# SensorBoard.net
KiCad netlist of a schematic drawn in Altium Designer
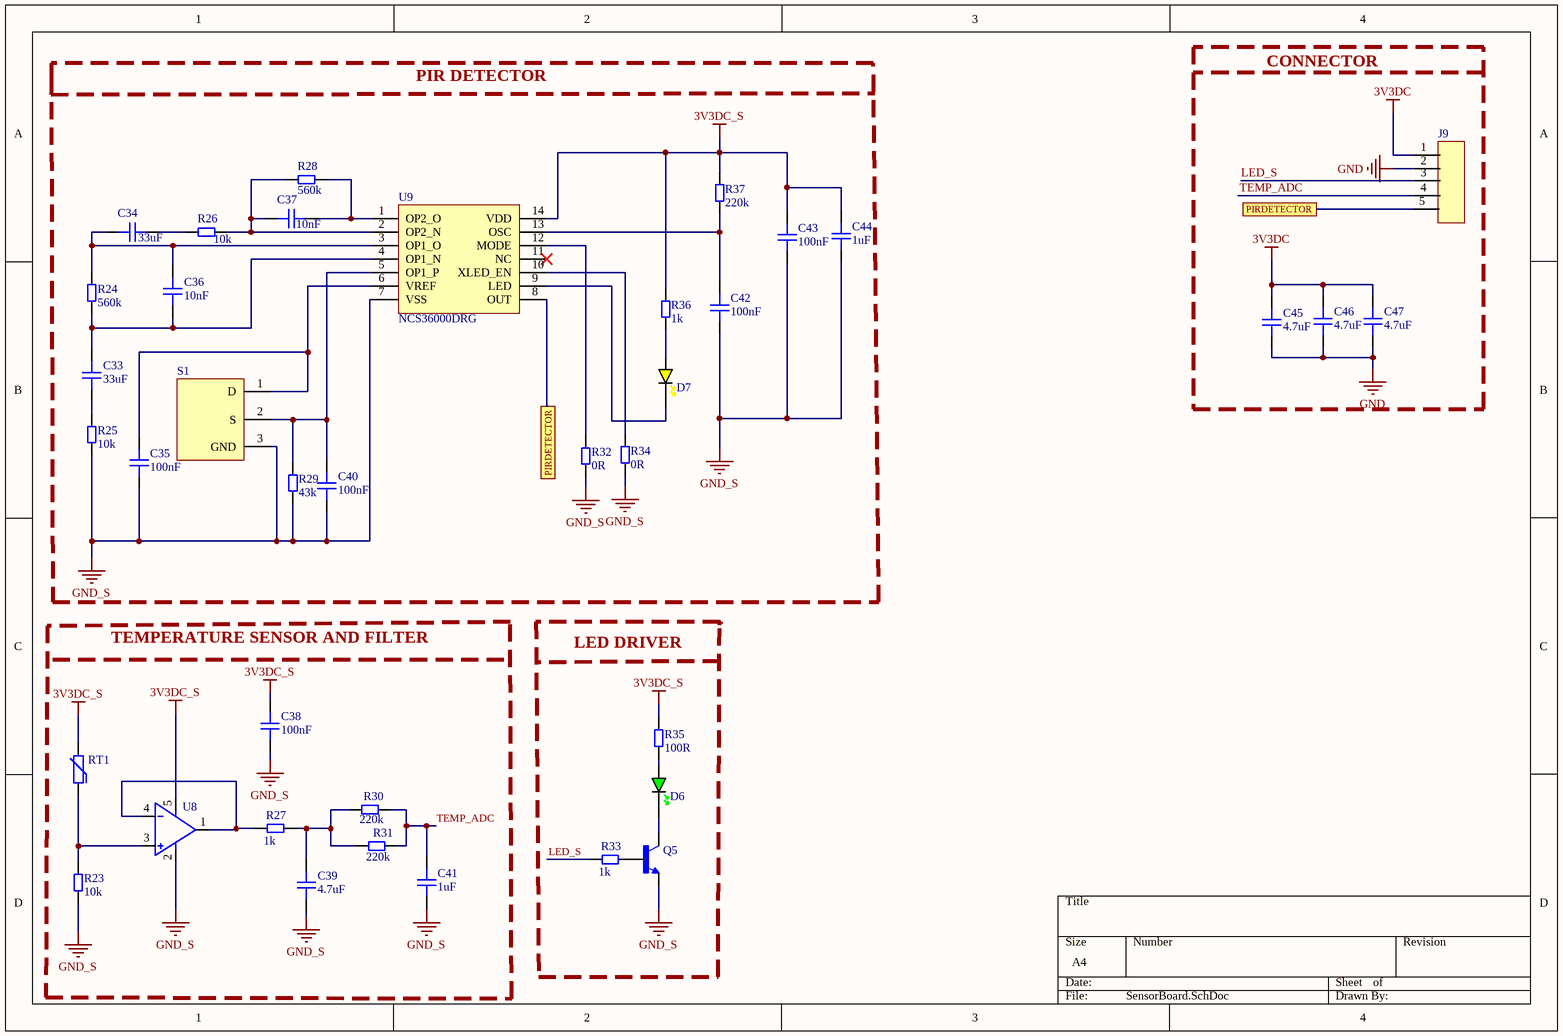
[diagram p0: SensorBoard.SchDoc]

(export (version "E")
  (design (tool "Eeschema 10.0.6"))
  (components
    (comp (ref "C33")
      (value "33uF")
      (footprint "CAP_0603")
      (description "Capacitor SMD 0603 10V")
      (libsource (lib "Integrated_Library1") (part "CAP_0603_10V"))
    )
    (comp (ref "C34")
      (value "33uF")
      (footprint "CAP_0603")
      (description "Capacitor SMD 0603 10V")
      (libsource (lib "Integrated_Library1") (part "CAP_0603_10V"))
    )
    (comp (ref "C35")
      (value "100nF")
      (footprint "CAP_0603")
      (description "Capacitor SMD 0603 10V")
      (libsource (lib "Integrated_Library1") (part "CAP_0603_10V"))
    )
    (comp (ref "C36")
      (value "10nF")
      (footprint "CAP_0603")
      (description "Capacitor SMD 0603 10V")
      (libsource (lib "Integrated_Library1") (part "CAP_0603_10V"))
    )
    (comp (ref "C37")
      (value "10nF")
      (footprint "CAP_0603")
      (description "Capacitor SMD 0603 10V")
      (libsource (lib "Integrated_Library1") (part "CAP_0603_10V"))
    )
    (comp (ref "C38")
      (value "100nF")
      (footprint "CAP_0603")
      (description "Capacitor SMD 0603 10V")
      (libsource (lib "Integrated_Library1") (part "CAP_0603_10V"))
    )
    (comp (ref "C39")
      (value "4.7uF")
      (footprint "CAP_0603")
      (description "Capacitor SMD 0603 10V")
      (libsource (lib "Integrated_Library1") (part "CAP_0603_10V"))
    )
    (comp (ref "C40")
      (value "100nF")
      (footprint "CAP_0603")
      (description "Capacitor SMD 0603 10V")
      (libsource (lib "Integrated_Library1") (part "CAP_0603_10V"))
    )
    (comp (ref "C41")
      (value "1uF")
      (footprint "CAP_0603")
      (description "Capacitor SMD 0603 10V")
      (libsource (lib "Integrated_Library1") (part "CAP_0603_10V"))
    )
    (comp (ref "C42")
      (value "100nF")
      (footprint "CAP_0603")
      (description "Capacitor SMD 0603 10V")
      (libsource (lib "Integrated_Library1") (part "CAP_0603_10V"))
    )
    (comp (ref "C43")
      (value "100nF")
      (footprint "CAP_0603")
      (description "Capacitor SMD 0603 10V")
      (libsource (lib "Integrated_Library1") (part "CAP_0603_10V"))
    )
    (comp (ref "C44")
      (value "1uF")
      (footprint "CAP_0603")
      (description "Capacitor SMD 0603 10V")
      (libsource (lib "Integrated_Library1") (part "CAP_0603_10V"))
    )
    (comp (ref "C45")
      (value "4.7uF")
      (footprint "CAP_0603")
      (description "Capacitor SMD 0603 10V")
      (libsource (lib "Integrated_Library1") (part "CAP_0603_10V"))
    )
    (comp (ref "C46")
      (value "4.7uF")
      (footprint "CAP_0603")
      (description "Capacitor SMD 0603 10V")
      (libsource (lib "Integrated_Library1") (part "CAP_0603_10V"))
    )
    (comp (ref "C47")
      (value "4.7uF")
      (footprint "CAP_0603")
      (description "Capacitor SMD 0603 10V")
      (libsource (lib "Integrated_Library1") (part "CAP_0603_10V"))
    )
    (comp (ref "D6")
      (value "GREEN")
      (footprint "LED_0603_GREEN")
      (description "LED 0603 GREEN SMD")
      (fields (field (name "DESIGNER") "ZehraOzkan"))
      (libsource (lib "Integrated_Library1") (part "LED_0603_GREEN"))
    )
    (comp (ref "D7")
      (value "YELLOW")
      (footprint "LED_0603_YELLOW")
      (description "LED 0603 YELLOW SMD")
      (fields (field (name "DESIGNER") "ZehraOzkan"))
      (libsource (lib "Integrated_Library1") (part "LED_0603_YELLOW"))
    )
    (comp (ref "J9")
      (value "Terminal_Block_Header")
      (footprint "HEADER_5")
      (description "5 pin Female")
      (fields (field (name "DESIGNER") "ZehraOzkan"))
      (libsource (lib "Integrated_Library1") (part "Terminal_Block_Header"))
    )
    (comp (ref "Q5")
      (value "BC237")
      (footprint "BC237")
      (description "Transistor NPN BC237B MOTOROLA milliampere=100 V=45 R204")
      (fields
        (field (name "MANUFACTURER") "ON Semiconductor / Fairchild")
        (field (name "MANUFACTURER PART NUMBER") "BC237B")
        (field (name "DESIGNER") "ZehraOzkan")
      )
      (libsource (lib "Integrated_Library1") (part "BC237"))
    )
    (comp (ref "R23")
      (value "10k")
      (footprint "RES-0805")
      (description "Res SMD 0805 10K 1% 0.125W T.C.100PPM")
      (fields
        (field (name "MANUFACTURER") "Yageo")
        (field (name "MANUFACTURER PART NUMBER") "RC0805FR-0710KL")
        (field (name "DESIGNER") "ZehraOzkan")
      )
      (libsource (lib "Integrated_Library1") (part "RES-0805-10k"))
    )
    (comp (ref "R24")
      (value "560k")
      (footprint "RES-0805")
      (description "Res SMD 0805 10K 1% 0.125W T.C.100PPM")
      (fields
        (field (name "MANUFACTURER") "Yageo")
        (field (name "MANUFACTURER PART NUMBER") "RC0805FR-0710KL")
        (field (name "DESIGNER") "ZehraOzkan")
      )
      (libsource (lib "Integrated_Library1") (part "RES-0805-10k"))
    )
    (comp (ref "R25")
      (value "10k")
      (footprint "RES-0805")
      (description "Res SMD 0805 10K 1% 0.125W T.C.100PPM")
      (fields
        (field (name "MANUFACTURER") "Yageo")
        (field (name "MANUFACTURER PART NUMBER") "RC0805FR-0710KL")
        (field (name "DESIGNER") "ZehraOzkan")
      )
      (libsource (lib "Integrated_Library1") (part "RES-0805-10k"))
    )
    (comp (ref "R26")
      (value "10k")
      (footprint "RES-0805")
      (description "Res SMD 0805 10K 1% 0.125W T.C.100PPM")
      (fields
        (field (name "MANUFACTURER") "Yageo")
        (field (name "MANUFACTURER PART NUMBER") "RC0805FR-0710KL")
        (field (name "DESIGNER") "ZehraOzkan")
      )
      (libsource (lib "Integrated_Library1") (part "RES-0805-10k"))
    )
    (comp (ref "R27")
      (value "1k")
      (footprint "RES-0805")
      (description "Res SMD 0805 10K 1% 0.125W T.C.100PPM")
      (fields
        (field (name "MANUFACTURER") "Yageo")
        (field (name "MANUFACTURER PART NUMBER") "RC0805FR-0710KL")
        (field (name "DESIGNER") "ZehraOzkan")
      )
      (libsource (lib "Integrated_Library1") (part "RES-0805-10k"))
    )
    (comp (ref "R28")
      (value "560k")
      (footprint "RES-0805")
      (description "Res SMD 0805 10K 1% 0.125W T.C.100PPM")
      (fields
        (field (name "MANUFACTURER") "Yageo")
        (field (name "MANUFACTURER PART NUMBER") "RC0805FR-0710KL")
        (field (name "DESIGNER") "ZehraOzkan")
      )
      (libsource (lib "Integrated_Library1") (part "RES-0805-10k"))
    )
    (comp (ref "R29")
      (value "43k")
      (footprint "RES-0805")
      (description "Res SMD 0805 10K 1% 0.125W T.C.100PPM")
      (fields
        (field (name "MANUFACTURER") "Yageo")
        (field (name "MANUFACTURER PART NUMBER") "RC0805FR-0710KL")
        (field (name "DESIGNER") "ZehraOzkan")
      )
      (libsource (lib "Integrated_Library1") (part "RES-0805-10k"))
    )
    (comp (ref "R30")
      (value "220k")
      (footprint "RES-0805")
      (description "Res SMD 0805 10K 1% 0.125W T.C.100PPM")
      (fields
        (field (name "MANUFACTURER") "Yageo")
        (field (name "MANUFACTURER PART NUMBER") "RC0805FR-0710KL")
        (field (name "DESIGNER") "ZehraOzkan")
      )
      (libsource (lib "Integrated_Library1") (part "RES-0805-10k"))
    )
    (comp (ref "R31")
      (value "220k")
      (footprint "RES-0805")
      (description "Res SMD 0805 10K 1% 0.125W T.C.100PPM")
      (fields
        (field (name "MANUFACTURER") "Yageo")
        (field (name "MANUFACTURER PART NUMBER") "RC0805FR-0710KL")
        (field (name "DESIGNER") "ZehraOzkan")
      )
      (libsource (lib "Integrated_Library1") (part "RES-0805-10k"))
    )
    (comp (ref "R32")
      (value "0R")
      (footprint "RES-0805")
      (description "Res SMD 0805 10K 1% 0.125W T.C.100PPM")
      (fields
        (field (name "MANUFACTURER") "Yageo")
        (field (name "MANUFACTURER PART NUMBER") "RC0805FR-0710KL")
        (field (name "DESIGNER") "ZehraOzkan")
      )
      (libsource (lib "Integrated_Library1") (part "RES-0805-10k"))
    )
    (comp (ref "R33")
      (value "1k")
      (footprint "RES-0805")
      (description "Res SMD 0805 10K 1% 0.125W T.C.100PPM")
      (fields
        (field (name "MANUFACTURER") "Yageo")
        (field (name "MANUFACTURER PART NUMBER") "RC0805FR-0710KL")
        (field (name "DESIGNER") "ZehraOzkan")
      )
      (libsource (lib "Integrated_Library1") (part "RES-0805-10k"))
    )
    (comp (ref "R34")
      (value "0R")
      (footprint "RES-0805")
      (description "Res SMD 0805 10K 1% 0.125W T.C.100PPM")
      (fields
        (field (name "MANUFACTURER") "Yageo")
        (field (name "MANUFACTURER PART NUMBER") "RC0805FR-0710KL")
        (field (name "DESIGNER") "ZehraOzkan")
      )
      (libsource (lib "Integrated_Library1") (part "RES-0805-10k"))
    )
    (comp (ref "R35")
      (value "100R")
      (footprint "RES-0805")
      (description "Res SMD 0805 10K 1% 0.125W T.C.100PPM")
      (fields
        (field (name "MANUFACTURER") "Yageo")
        (field (name "MANUFACTURER PART NUMBER") "RC0805FR-0710KL")
        (field (name "DESIGNER") "ZehraOzkan")
      )
      (libsource (lib "Integrated_Library1") (part "RES-0805-10k"))
    )
    (comp (ref "R36")
      (value "1k")
      (footprint "RES-0805")
      (description "Res SMD 0805 10K 1% 0.125W T.C.100PPM")
      (fields
        (field (name "MANUFACTURER") "Yageo")
        (field (name "MANUFACTURER PART NUMBER") "RC0805FR-0710KL")
        (field (name "DESIGNER") "ZehraOzkan")
      )
      (libsource (lib "Integrated_Library1") (part "RES-0805-10k"))
    )
    (comp (ref "R37")
      (value "220k")
      (footprint "RES-0805")
      (description "Res SMD 0805 10K 1% 0.125W T.C.100PPM")
      (fields
        (field (name "MANUFACTURER") "Yageo")
        (field (name "MANUFACTURER PART NUMBER") "RC0805FR-0710KL")
        (field (name "DESIGNER") "ZehraOzkan")
      )
      (libsource (lib "Integrated_Library1") (part "RES-0805-10k"))
    )
    (comp (ref "RT1")
      (value "TFPT1206L1002FM")
      (footprint "RES_1206")
      (description "Thermistor PTC 10K Ohm 1% 2-Pin 1206 Surface Mount Solder Pad T/R Automotive")
      (fields
        (field (name "MANUFACTURER") "Vishay Dale")
        (field (name "TOLERANCE") "1%")
        (field (name "DESIGNER") "ZehraOzkan")
      )
      (libsource (lib "Integrated_Library1") (part "TFPT1206L1002FM"))
    )
    (comp (ref "S1")
      (value "LHI 878/3902")
      (footprint "LHI 878")
      (description "SENSOR PYRO DETECTOR DUAL MOTION")
      (fields
        (field (name "MANUFACTURER") "Excelitas")
        (field (name "MANUFACTURER PART NUMBER") "LHI878/3902")
        (field (name "DESIGNER") "ZehraOzkan")
      )
      (libsource (lib "Integrated_Library1") (part "LHI 878/3902"))
    )
    (comp (ref "U8")
      (value "OPA314AIDBVR")
      (footprint "SOT-23-5")
      (description "IC OPAMP GP 3MHZ RRO SOT23-5")
      (fields (field (name "MANUFACTURER") "Texas Instruments") (field (name "DESIGNER") "ZehraOzkan"))
      (libsource (lib "Integrated_Library1") (part "OPA314AIDBVR"))
    )
    (comp (ref "U9")
      (value "NCS36000DRG")
      (footprint "SOIC-14")
      (description "NCS36000 Series Single 5.75V Passive Infrared Detector Controller (PIR) -SOIC-14")
      (fields (field (name "MANUFACTURER") "ON Semiconductor") (field (name "DESIGNER") "ZehraOzkan"))
      (libsource (lib "Integrated_Library1") (part "NCS36000DRG"))
    )
  )
  (nets
    (net (code "1") (name "/LED_S") (class "Default")
      (node (ref "J9") (pin "3") (pinfunction "3_3") (pintype "passive"))
      (node (ref "R33") (pin "2") (pinfunction "2_2") (pintype "passive"))
    )
    (net (code "2") (name "/PIRDETECTOR") (class "Default")
      (node (ref "J9") (pin "5") (pinfunction "5_5") (pintype "passive"))
      (node (ref "U9") (pin "8") (pinfunction "OUT_8") (pintype "passive"))
    )
    (net (code "3") (name "/TEMP_ADC") (class "Default")
      (node (ref "C41") (pin "2") (pinfunction "2_2") (pintype "passive"))
      (node (ref "J9") (pin "4") (pinfunction "4_4") (pintype "passive"))
      (node (ref "R30") (pin "1") (pinfunction "1_1") (pintype "passive"))
      (node (ref "R31") (pin "1") (pinfunction "1_1") (pintype "passive"))
    )
    (net (code "4") (name "3V3DC") (class "Default")
      (node (ref "C45") (pin "2") (pinfunction "2_2") (pintype "passive"))
      (node (ref "C46") (pin "2") (pinfunction "2_2") (pintype "passive"))
      (node (ref "C47") (pin "2") (pinfunction "2_2") (pintype "passive"))
      (node (ref "J9") (pin "1") (pinfunction "1_1") (pintype "passive"))
    )
    (net (code "5") (name "3V3DC_S") (class "Default")
      (node (ref "C38") (pin "2") (pinfunction "2_2") (pintype "passive"))
      (node (ref "C43") (pin "2") (pinfunction "2_2") (pintype "passive"))
      (node (ref "C44") (pin "2") (pinfunction "2_2") (pintype "passive"))
      (node (ref "R35") (pin "1") (pinfunction "1_1") (pintype "passive"))
      (node (ref "R36") (pin "1") (pinfunction "1_1") (pintype "passive"))
      (node (ref "R37") (pin "1") (pinfunction "1_1") (pintype "passive"))
      (node (ref "RT1") (pin "2") (pinfunction "2_2") (pintype "passive"))
      (node (ref "U8") (pin "5") (pintype "passive"))
      (node (ref "U9") (pin "14") (pinfunction "VDD_14") (pintype "passive"))
    )
    (net (code "6") (name "GND") (class "Default")
      (node (ref "C45") (pin "1") (pinfunction "1_1") (pintype "passive"))
      (node (ref "C46") (pin "1") (pinfunction "1_1") (pintype "passive"))
      (node (ref "C47") (pin "1") (pinfunction "1_1") (pintype "passive"))
      (node (ref "J9") (pin "2") (pinfunction "2_2") (pintype "passive"))
    )
    (net (code "7") (name "GND_S") (class "Default")
      (node (ref "C35") (pin "2") (pinfunction "2_2") (pintype "passive"))
      (node (ref "C38") (pin "1") (pinfunction "1_1") (pintype "passive"))
      (node (ref "C39") (pin "1") (pinfunction "1_1") (pintype "passive"))
      (node (ref "C40") (pin "2") (pinfunction "2_2") (pintype "passive"))
      (node (ref "C41") (pin "1") (pinfunction "1_1") (pintype "passive"))
      (node (ref "C42") (pin "1") (pinfunction "1_1") (pintype "passive"))
      (node (ref "C43") (pin "1") (pinfunction "1_1") (pintype "passive"))
      (node (ref "C44") (pin "1") (pinfunction "1_1") (pintype "passive"))
      (node (ref "Q5") (pin "1") (pinfunction "E_1") (pintype "passive"))
      (node (ref "R23") (pin "1") (pinfunction "1_1") (pintype "passive"))
      (node (ref "R25") (pin "1") (pinfunction "1_1") (pintype "passive"))
      (node (ref "R29") (pin "1") (pinfunction "1_1") (pintype "passive"))
      (node (ref "R32") (pin "2") (pinfunction "2_2") (pintype "passive"))
      (node (ref "R34") (pin "2") (pinfunction "2_2") (pintype "passive"))
      (node (ref "S1") (pin "3") (pinfunction "GND_3") (pintype "passive"))
      (node (ref "U8") (pin "2") (pintype "passive"))
      (node (ref "U9") (pin "7") (pinfunction "VSS_7") (pintype "passive"))
    )
    (net (code "8") (name "Net-(C33-Pad2)") (class "Default")
      (node (ref "C33") (pin "2") (pinfunction "2_2") (pintype "passive"))
      (node (ref "R25") (pin "2") (pinfunction "2_2") (pintype "passive"))
    )
    (net (code "9") (name "Net-(C34-Pad1)") (class "Default")
      (node (ref "C34") (pin "1") (pinfunction "1_1") (pintype "passive"))
      (node (ref "R26") (pin "1") (pinfunction "1_1") (pintype "passive"))
    )
    (net (code "10") (name "Net-(C39-Pad2)") (class "Default")
      (node (ref "C39") (pin "2") (pinfunction "2_2") (pintype "passive"))
      (node (ref "R27") (pin "1") (pinfunction "1_1") (pintype "passive"))
      (node (ref "R30") (pin "2") (pinfunction "2_2") (pintype "passive"))
      (node (ref "R31") (pin "2") (pinfunction "2_2") (pintype "passive"))
    )
    (net (code "11") (name "Net-(D6-PadA)") (class "Default")
      (node (ref "D6") (pin "A") (pinfunction "A_A") (pintype "passive"))
      (node (ref "R35") (pin "2") (pinfunction "2_2") (pintype "passive"))
    )
    (net (code "12") (name "Net-(D7-PadA)") (class "Default")
      (node (ref "D7") (pin "A") (pinfunction "A_A") (pintype "passive"))
      (node (ref "R36") (pin "2") (pinfunction "2_2") (pintype "passive"))
    )
    (net (code "13") (name "Net-(Q5-B)") (class "Default")
      (node (ref "Q5") (pin "2") (pinfunction "B_2") (pintype "passive"))
      (node (ref "R33") (pin "1") (pinfunction "1_1") (pintype "passive"))
    )
    (net (code "14") (name "Net-(Q5-C)") (class "Default")
      (node (ref "D6") (pin "K") (pinfunction "K_K") (pintype "passive"))
      (node (ref "Q5") (pin "3") (pinfunction "C_3") (pintype "passive"))
    )
    (net (code "15") (name "Net-(R23-Pad2)") (class "Default")
      (node (ref "R23") (pin "2") (pinfunction "2_2") (pintype "passive"))
      (node (ref "RT1") (pin "1") (pinfunction "1_1") (pintype "passive"))
      (node (ref "U8") (pin "3") (pintype "passive"))
    )
    (net (code "16") (name "Net-(R27-Pad2)") (class "Default")
      (node (ref "R27") (pin "2") (pinfunction "2_2") (pintype "passive"))
      (node (ref "U8") (pin "1") (pintype "passive"))
      (node (ref "U8") (pin "4") (pintype "passive"))
    )
    (net (code "17") (name "Net-(S1-D)") (class "Default")
      (node (ref "C35") (pin "1") (pinfunction "1_1") (pintype "passive"))
      (node (ref "S1") (pin "1") (pinfunction "D_1") (pintype "passive"))
      (node (ref "U9") (pin "6") (pinfunction "VREF_6") (pintype "passive"))
    )
    (net (code "18") (name "Net-(S1-S)") (class "Default")
      (node (ref "C40") (pin "1") (pinfunction "1_1") (pintype "passive"))
      (node (ref "R29") (pin "2") (pinfunction "2_2") (pintype "passive"))
      (node (ref "S1") (pin "2") (pinfunction "S_2") (pintype "passive"))
      (node (ref "U9") (pin "5") (pinfunction "OP1_P_5") (pintype "passive"))
    )
    (net (code "19") (name "Net-(U9-LED)") (class "Default")
      (node (ref "D7") (pin "K") (pinfunction "K_K") (pintype "passive"))
      (node (ref "U9") (pin "9") (pinfunction "LED_9") (pintype "passive"))
    )
    (net (code "20") (name "Net-(U9-MODE)") (class "Default")
      (node (ref "R32") (pin "1") (pinfunction "1_1") (pintype "passive"))
      (node (ref "U9") (pin "12") (pinfunction "MODE_12") (pintype "passive"))
    )
    (net (code "21") (name "Net-(U9-OP1_N)") (class "Default")
      (node (ref "C33") (pin "1") (pinfunction "1_1") (pintype "passive"))
      (node (ref "C36") (pin "2") (pinfunction "2_2") (pintype "passive"))
      (node (ref "R24") (pin "1") (pinfunction "1_1") (pintype "passive"))
      (node (ref "U9") (pin "4") (pinfunction "OP1_N_4") (pintype "passive"))
    )
    (net (code "22") (name "Net-(U9-OP1_O)") (class "Default")
      (node (ref "C34") (pin "2") (pinfunction "2_2") (pintype "passive"))
      (node (ref "C36") (pin "1") (pinfunction "1_1") (pintype "passive"))
      (node (ref "R24") (pin "2") (pinfunction "2_2") (pintype "passive"))
      (node (ref "U9") (pin "3") (pinfunction "OP1_O_3") (pintype "passive"))
    )
    (net (code "23") (name "Net-(U9-OP2_N)") (class "Default")
      (node (ref "C37") (pin "2") (pinfunction "2_2") (pintype "passive"))
      (node (ref "R26") (pin "2") (pinfunction "2_2") (pintype "passive"))
      (node (ref "R28") (pin "1") (pinfunction "1_1") (pintype "passive"))
      (node (ref "U9") (pin "2") (pinfunction "OP2_N_2") (pintype "passive"))
    )
    (net (code "24") (name "Net-(U9-OP2_O)") (class "Default")
      (node (ref "C37") (pin "1") (pinfunction "1_1") (pintype "passive"))
      (node (ref "R28") (pin "2") (pinfunction "2_2") (pintype "passive"))
      (node (ref "U9") (pin "1") (pinfunction "OP2_O_1") (pintype "passive"))
    )
    (net (code "25") (name "Net-(U9-OSC)") (class "Default")
      (node (ref "C42") (pin "2") (pinfunction "2_2") (pintype "passive"))
      (node (ref "R37") (pin "2") (pinfunction "2_2") (pintype "passive"))
      (node (ref "U9") (pin "13") (pinfunction "OSC_13") (pintype "passive"))
    )
    (net (code "26") (name "Net-(U9-XLED_EN)") (class "Default")
      (node (ref "R34") (pin "1") (pinfunction "1_1") (pintype "passive"))
      (node (ref "U9") (pin "10") (pinfunction "XLED_EN_10") (pintype "passive"))
    )
    (net (code "27") (name "unconnected-(U9-NC-Pad11)") (class "Default")
      (node (ref "U9") (pin "11") (pinfunction "NC_11") (pintype "passive+no_connect"))
    )
  )
)
